# prototype.net
KiCad netlist of a schematic drawn in EAGLE
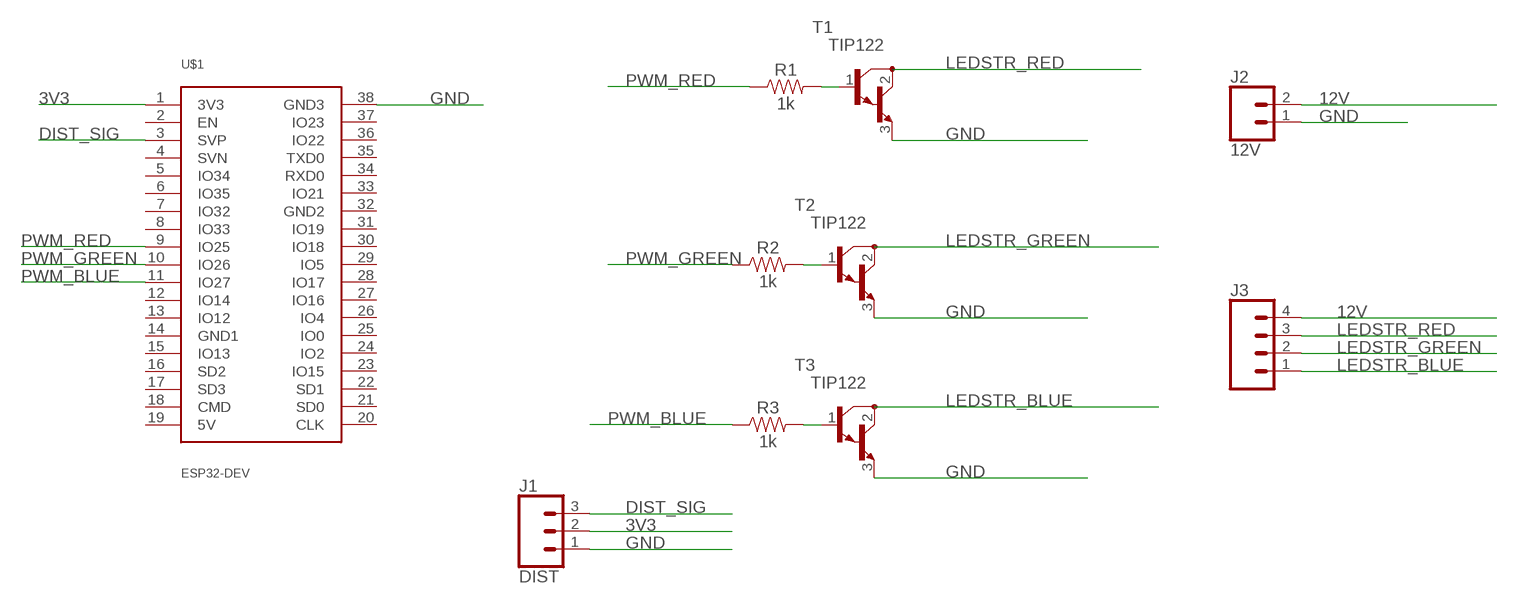
[diagram p0: schematic, sheet 1]

(export (version "E")
  (design (tool "Eeschema 10.0.6"))
  (components
    (comp (ref "J1")
      (value "DIST")
      (footprint "eagle-import:1X03_LONGPADS")
      (libsource (lib "eagle-import") (part "CONN_03LONGPADS"))
    )
    (comp (ref "J2")
      (value "12V")
      (footprint "eagle-import:1X02_LONGPADS")
      (libsource (lib "eagle-import") (part "CONN_02PTH3"))
    )
    (comp (ref "J3")
      (value "CONN_04LONGPADS")
      (footprint "eagle-import:1X04_LONGPADS")
      (libsource (lib "eagle-import") (part "CONN_04LONGPADS"))
    )
    (comp (ref "R1")
      (value "1k")
      (footprint "eagle-import:AXIAL-0.3")
      (libsource (lib "eagle-import") (part "1KOHM-HORIZ-1/4W-1%"))
    )
    (comp (ref "R2")
      (value "1k")
      (footprint "eagle-import:AXIAL-0.3")
      (libsource (lib "eagle-import") (part "1KOHM-HORIZ-1/4W-1%"))
    )
    (comp (ref "R3")
      (value "1k")
      (footprint "eagle-import:AXIAL-0.3")
      (libsource (lib "eagle-import") (part "1KOHM-HORIZ-1/4W-1%"))
    )
    (comp (ref "T1")
      (value "TIP122")
      (footprint "eagle-import:TO220")
      (libsource (lib "eagle-import") (part "TIP122"))
    )
    (comp (ref "T2")
      (value "TIP122")
      (footprint "eagle-import:TO220")
      (libsource (lib "eagle-import") (part "TIP122"))
    )
    (comp (ref "T3")
      (value "TIP122")
      (footprint "eagle-import:TO220")
      (libsource (lib "eagle-import") (part "TIP122"))
    )
    (comp (ref "U$1")
      (value "ESP32-DEV")
      (footprint "eagle-import:ESP32-DEV")
      (libsource (lib "eagle-import") (part "ESP32-DEV"))
    )
  )
  (nets
    (net (code "1") (name "/3V3") (class "Default")
      (node (ref "J1") (pin "2") (pinfunction "2_2") (pintype "passive"))
      (node (ref "U$1") (pin "1") (pinfunction "3V3_1") (pintype "bidirectional"))
    )
    (net (code "2") (name "/12V") (class "Default")
      (node (ref "J2") (pin "2") (pinfunction "2_2") (pintype "passive"))
      (node (ref "J3") (pin "4") (pinfunction "4_4") (pintype "passive"))
    )
    (net (code "3") (name "/DIST_SIG") (class "Default")
      (node (ref "J1") (pin "3") (pinfunction "3_3") (pintype "passive"))
      (node (ref "U$1") (pin "3") (pinfunction "SVP_3") (pintype "bidirectional"))
    )
    (net (code "4") (name "/GND") (class "Default")
      (node (ref "J1") (pin "1") (pinfunction "1_1") (pintype "passive"))
      (node (ref "J2") (pin "1") (pinfunction "1_1") (pintype "passive"))
      (node (ref "T1") (pin "3") (pinfunction "E_3") (pintype "passive"))
      (node (ref "T2") (pin "3") (pinfunction "E_3") (pintype "passive"))
      (node (ref "T3") (pin "3") (pinfunction "E_3") (pintype "passive"))
      (node (ref "U$1") (pin "38") (pinfunction "GND3_38") (pintype "bidirectional"))
    )
    (net (code "5") (name "/LEDSTR_BLUE") (class "Default")
      (node (ref "J3") (pin "1") (pinfunction "1_1") (pintype "passive"))
      (node (ref "T3") (pin "2") (pinfunction "C_2") (pintype "passive"))
    )
    (net (code "6") (name "/LEDSTR_GREEN") (class "Default")
      (node (ref "J3") (pin "2") (pinfunction "2_2") (pintype "passive"))
      (node (ref "T2") (pin "2") (pinfunction "C_2") (pintype "passive"))
    )
    (net (code "7") (name "/LEDSTR_RED") (class "Default")
      (node (ref "J3") (pin "3") (pinfunction "3_3") (pintype "passive"))
      (node (ref "T1") (pin "2") (pinfunction "C_2") (pintype "passive"))
    )
    (net (code "8") (name "/PWM_BLUE") (class "Default")
      (node (ref "R3") (pin "P$1") (pinfunction "1_P$1") (pintype "passive"))
      (node (ref "U$1") (pin "11") (pinfunction "IO27_11") (pintype "bidirectional"))
    )
    (net (code "9") (name "/PWM_GREEN") (class "Default")
      (node (ref "R2") (pin "P$1") (pinfunction "1_P$1") (pintype "passive"))
      (node (ref "U$1") (pin "10") (pinfunction "IO26_10") (pintype "bidirectional"))
    )
    (net (code "10") (name "/PWM_RED") (class "Default")
      (node (ref "R1") (pin "P$1") (pinfunction "1_P$1") (pintype "passive"))
      (node (ref "U$1") (pin "9") (pinfunction "IO25_9") (pintype "bidirectional"))
    )
    (net (code "11") (name "Net-(R1-2)") (class "Default")
      (node (ref "R1") (pin "P$2") (pinfunction "2_P$2") (pintype "passive"))
      (node (ref "T1") (pin "1") (pinfunction "B_1") (pintype "passive"))
    )
    (net (code "12") (name "Net-(R2-2)") (class "Default")
      (node (ref "R2") (pin "P$2") (pinfunction "2_P$2") (pintype "passive"))
      (node (ref "T2") (pin "1") (pinfunction "B_1") (pintype "passive"))
    )
    (net (code "13") (name "Net-(R3-2)") (class "Default")
      (node (ref "R3") (pin "P$2") (pinfunction "2_P$2") (pintype "passive"))
      (node (ref "T3") (pin "1") (pinfunction "B_1") (pintype "passive"))
    )
    (net (code "14") (name "unconnected-(U$1-5V-Pad19)") (class "Default")
      (node (ref "U$1") (pin "19") (pinfunction "5V_19") (pintype "bidirectional"))
    )
    (net (code "15") (name "unconnected-(U$1-CLK-Pad20)") (class "Default")
      (node (ref "U$1") (pin "20") (pinfunction "CLK_20") (pintype "bidirectional"))
    )
    (net (code "16") (name "unconnected-(U$1-CMD-Pad18)") (class "Default")
      (node (ref "U$1") (pin "18") (pinfunction "CMD_18") (pintype "bidirectional"))
    )
    (net (code "17") (name "unconnected-(U$1-EN-Pad2)") (class "Default")
      (node (ref "U$1") (pin "2") (pinfunction "EN_2") (pintype "bidirectional"))
    )
    (net (code "18") (name "unconnected-(U$1-GND1-Pad14)") (class "Default")
      (node (ref "U$1") (pin "14") (pinfunction "GND1_14") (pintype "bidirectional"))
    )
    (net (code "19") (name "unconnected-(U$1-GND2-Pad32)") (class "Default")
      (node (ref "U$1") (pin "32") (pinfunction "GND2_32") (pintype "bidirectional"))
    )
    (net (code "20") (name "unconnected-(U$1-IO0-Pad25)") (class "Default")
      (node (ref "U$1") (pin "25") (pinfunction "IO0_25") (pintype "bidirectional"))
    )
    (net (code "21") (name "unconnected-(U$1-IO2-Pad24)") (class "Default")
      (node (ref "U$1") (pin "24") (pinfunction "IO2_24") (pintype "bidirectional"))
    )
    (net (code "22") (name "unconnected-(U$1-IO4-Pad26)") (class "Default")
      (node (ref "U$1") (pin "26") (pinfunction "IO4_26") (pintype "bidirectional"))
    )
    (net (code "23") (name "unconnected-(U$1-IO5-Pad29)") (class "Default")
      (node (ref "U$1") (pin "29") (pinfunction "IO5_29") (pintype "bidirectional"))
    )
    (net (code "24") (name "unconnected-(U$1-IO12-Pad13)") (class "Default")
      (node (ref "U$1") (pin "13") (pinfunction "IO12_13") (pintype "bidirectional"))
    )
    (net (code "25") (name "unconnected-(U$1-IO13-Pad15)") (class "Default")
      (node (ref "U$1") (pin "15") (pinfunction "IO13_15") (pintype "bidirectional"))
    )
    (net (code "26") (name "unconnected-(U$1-IO14-Pad12)") (class "Default")
      (node (ref "U$1") (pin "12") (pinfunction "IO14_12") (pintype "bidirectional"))
    )
    (net (code "27") (name "unconnected-(U$1-IO15-Pad23)") (class "Default")
      (node (ref "U$1") (pin "23") (pinfunction "IO15_23") (pintype "bidirectional"))
    )
    (net (code "28") (name "unconnected-(U$1-IO16-Pad27)") (class "Default")
      (node (ref "U$1") (pin "27") (pinfunction "IO16_27") (pintype "bidirectional"))
    )
    (net (code "29") (name "unconnected-(U$1-IO17-Pad28)") (class "Default")
      (node (ref "U$1") (pin "28") (pinfunction "IO17_28") (pintype "bidirectional"))
    )
    (net (code "30") (name "unconnected-(U$1-IO18-Pad30)") (class "Default")
      (node (ref "U$1") (pin "30") (pinfunction "IO18_30") (pintype "bidirectional"))
    )
    (net (code "31") (name "unconnected-(U$1-IO19-Pad31)") (class "Default")
      (node (ref "U$1") (pin "31") (pinfunction "IO19_31") (pintype "bidirectional"))
    )
    (net (code "32") (name "unconnected-(U$1-IO21-Pad33)") (class "Default")
      (node (ref "U$1") (pin "33") (pinfunction "IO21_33") (pintype "bidirectional"))
    )
    (net (code "33") (name "unconnected-(U$1-IO22-Pad36)") (class "Default")
      (node (ref "U$1") (pin "36") (pinfunction "IO22_36") (pintype "bidirectional"))
    )
    (net (code "34") (name "unconnected-(U$1-IO23-Pad37)") (class "Default")
      (node (ref "U$1") (pin "37") (pinfunction "IO23_37") (pintype "bidirectional"))
    )
    (net (code "35") (name "unconnected-(U$1-IO32-Pad7)") (class "Default")
      (node (ref "U$1") (pin "7") (pinfunction "IO32_7") (pintype "bidirectional"))
    )
    (net (code "36") (name "unconnected-(U$1-IO33-Pad8)") (class "Default")
      (node (ref "U$1") (pin "8") (pinfunction "IO33_8") (pintype "bidirectional"))
    )
    (net (code "37") (name "unconnected-(U$1-IO34-Pad5)") (class "Default")
      (node (ref "U$1") (pin "5") (pinfunction "IO34_5") (pintype "bidirectional"))
    )
    (net (code "38") (name "unconnected-(U$1-IO35-Pad6)") (class "Default")
      (node (ref "U$1") (pin "6") (pinfunction "IO35_6") (pintype "bidirectional"))
    )
    (net (code "39") (name "unconnected-(U$1-RXD0-Pad34)") (class "Default")
      (node (ref "U$1") (pin "34") (pinfunction "RXD0_34") (pintype "bidirectional"))
    )
    (net (code "40") (name "unconnected-(U$1-SD0-Pad21)") (class "Default")
      (node (ref "U$1") (pin "21") (pinfunction "SD0_21") (pintype "bidirectional"))
    )
    (net (code "41") (name "unconnected-(U$1-SD1-Pad22)") (class "Default")
      (node (ref "U$1") (pin "22") (pinfunction "SD1_22") (pintype "bidirectional"))
    )
    (net (code "42") (name "unconnected-(U$1-SD2-Pad16)") (class "Default")
      (node (ref "U$1") (pin "16") (pinfunction "SD2_16") (pintype "bidirectional"))
    )
    (net (code "43") (name "unconnected-(U$1-SD3-Pad17)") (class "Default")
      (node (ref "U$1") (pin "17") (pinfunction "SD3_17") (pintype "bidirectional"))
    )
    (net (code "44") (name "unconnected-(U$1-SVN-Pad4)") (class "Default")
      (node (ref "U$1") (pin "4") (pinfunction "SVN_4") (pintype "bidirectional"))
    )
    (net (code "45") (name "unconnected-(U$1-TXD0-Pad35)") (class "Default")
      (node (ref "U$1") (pin "35") (pinfunction "TXD0_35") (pintype "bidirectional"))
    )
  )
)
